# cellular.net
KiCad netlist of a schematic drawn in Altium Designer
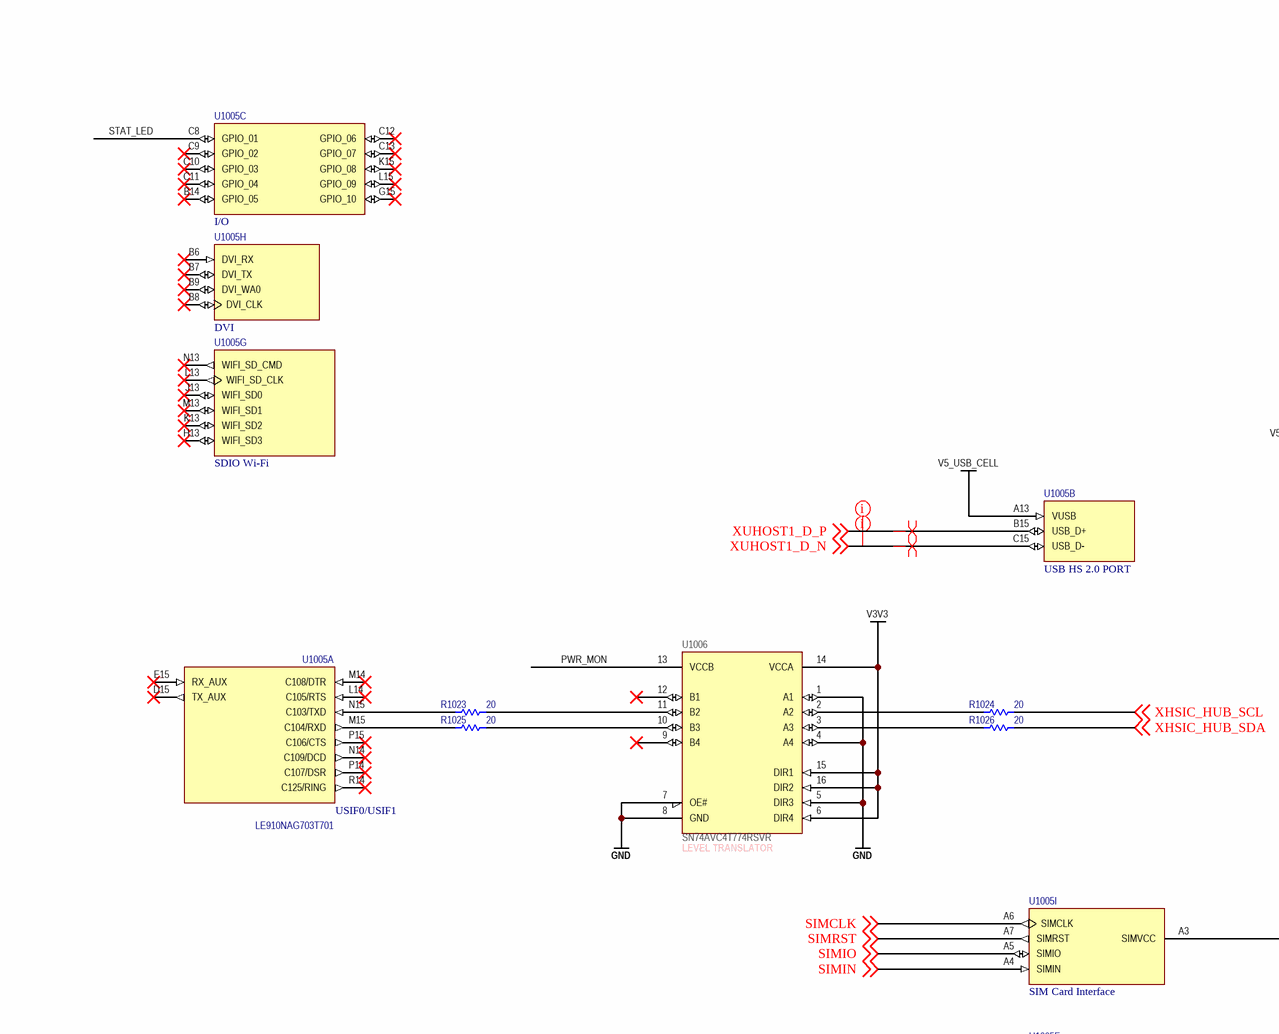
[diagram p0: cellular.SchDoc, top left]
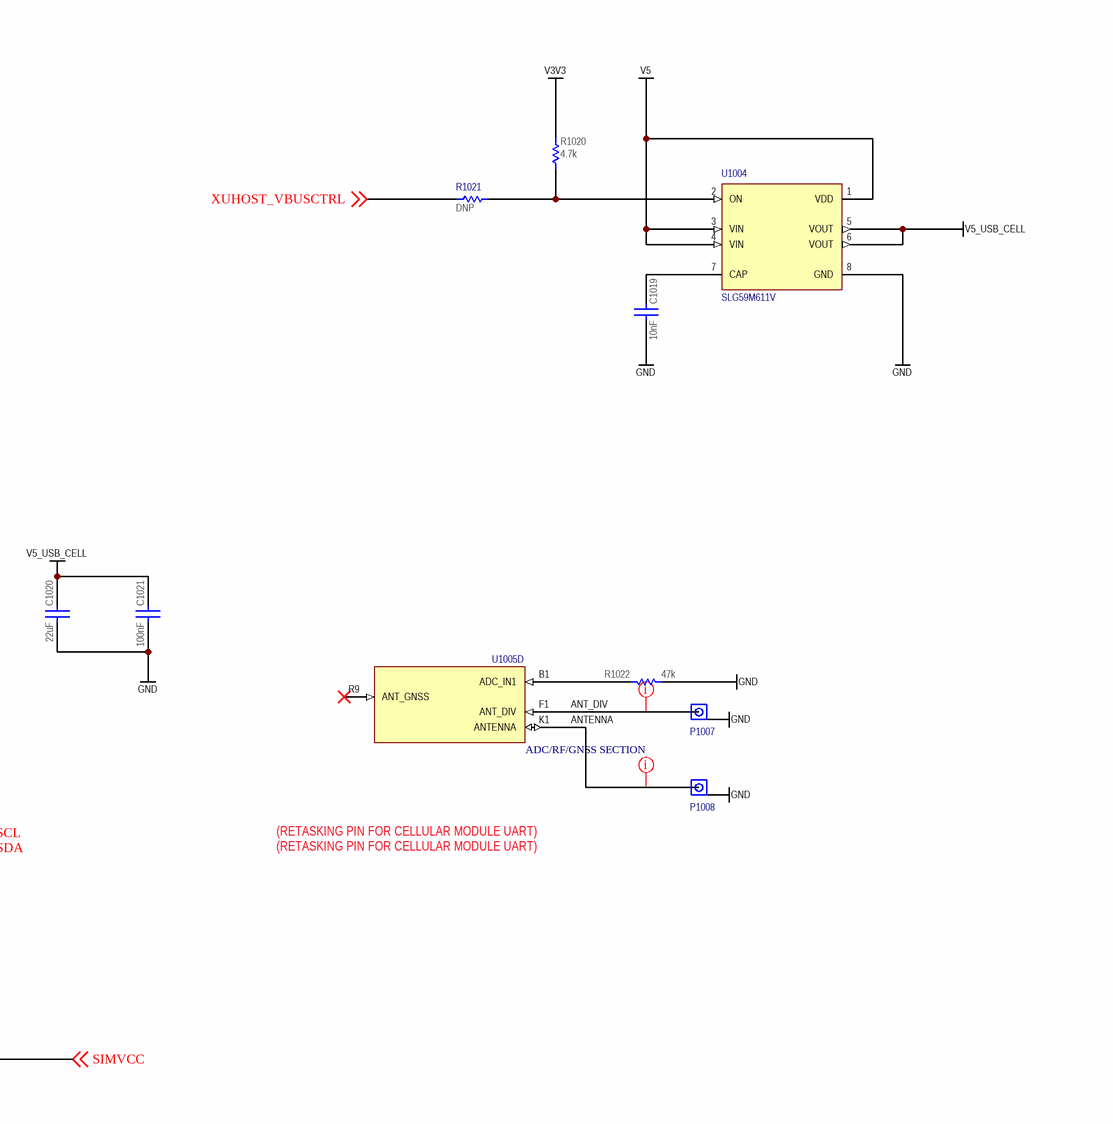
[diagram p1: cellular.SchDoc, top right]
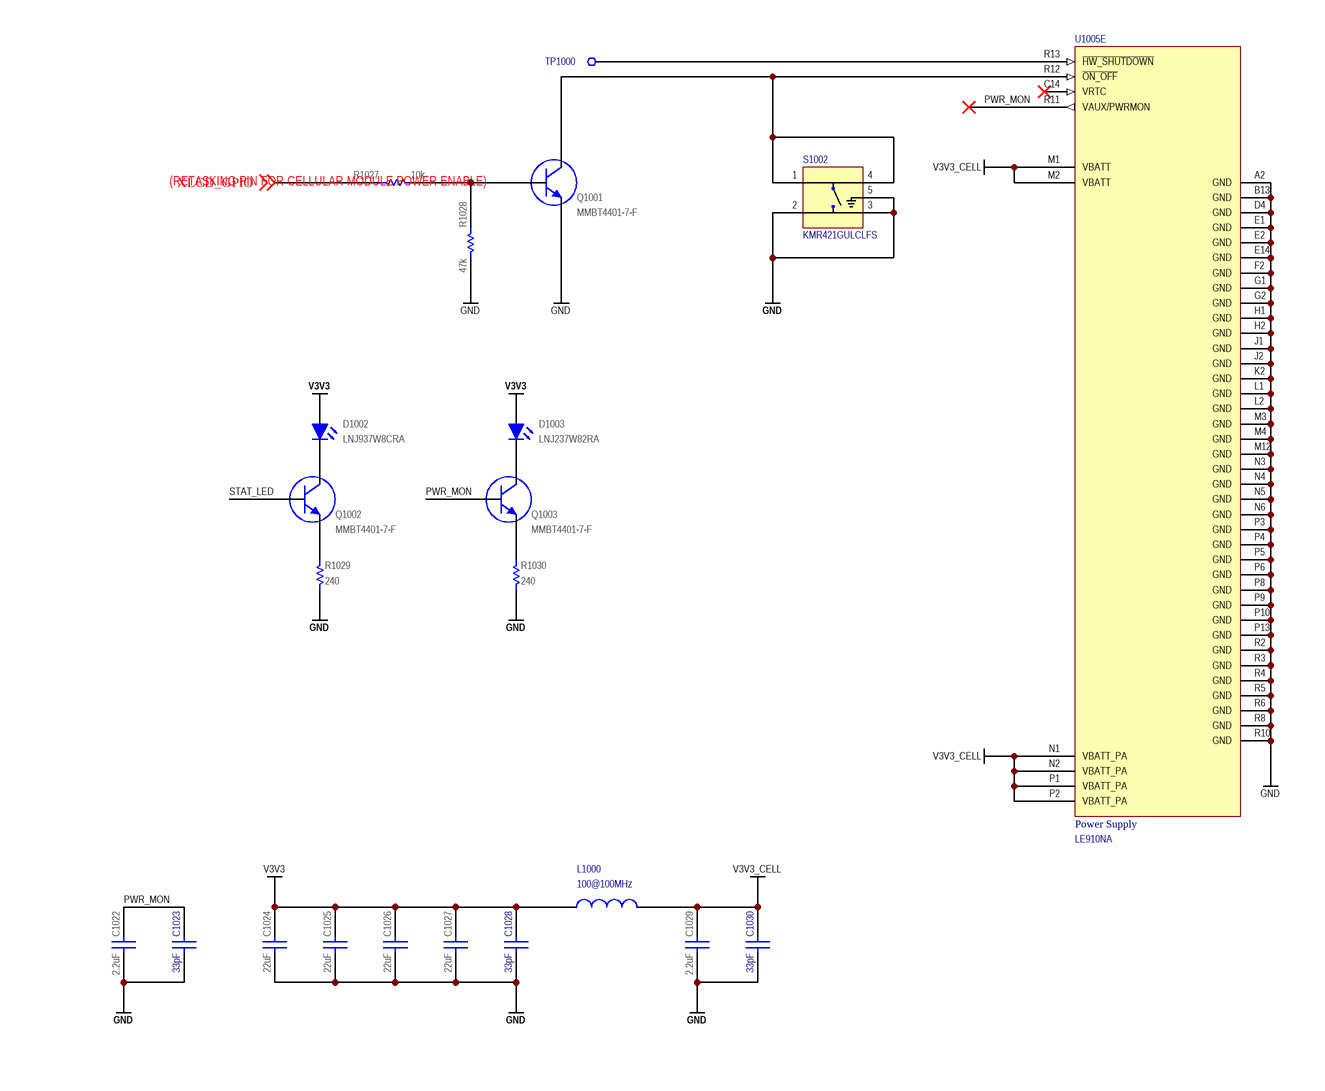
[diagram p2: cellular.SchDoc, bottom left]
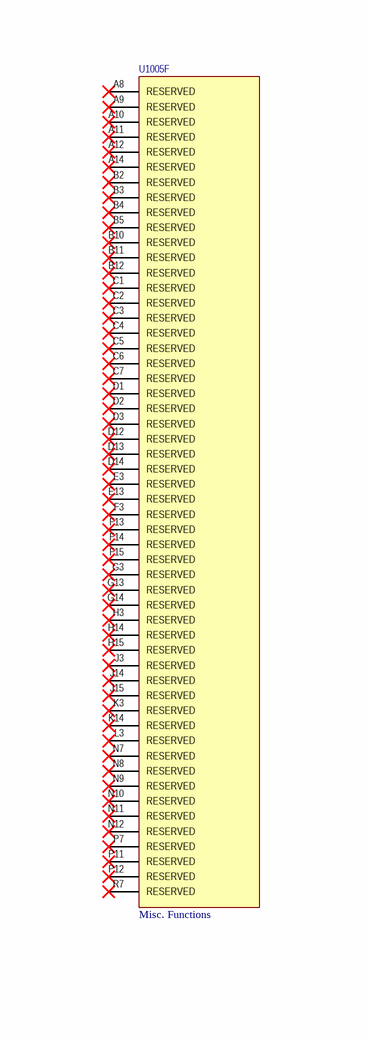
[diagram p3: cellular.SchDoc, bottom right]

(export (version "E")
  (design (tool "Eeschema 10.0.6"))
  (components
    (comp (ref "C1019")
      (value "10nF")
      (footprint "CAPC100X50X55L25N")
      (description "Ceramic Capacitor 10nF ±10% 50V X7R 0402")
      (fields (field (name "MANUFACTURER") "Murata") (field (name "TOLERANCE") "±10%"))
      (libsource (lib "generic") (part "CAP"))
    )
    (comp (ref "C1020")
      (value "22uF")
      (footprint "CAPC200X125X145L45N")
      (description "Ceramic Capacitor 22uF ±20% 10V X7S 0805")
      (fields (field (name "MANUFACTURER") "TDK") (field (name "TOLERANCE") "±20%"))
      (libsource (lib "generic") (part "CAP"))
    )
    (comp (ref "C1021")
      (value "100nF")
      (footprint "CAPC100X50X55L25N")
      (description "Ceramic Capacitor 100nF ±10% 50V X7R 0402")
      (fields (field (name "MANUFACTURER") "Murata") (field (name "TOLERANCE") "±10%"))
      (libsource (lib "generic") (part "CAP"))
    )
    (comp (ref "C1022")
      (value "2.2uF")
      (footprint "CAPC160X80X90L20N")
      (description "Ceramic Capacitor 2.2uF ±20% 10V X7R 0603")
      (fields (field (name "MANUFACTURER") "TDK") (field (name "TOLERANCE") "±20%"))
      (libsource (lib "generic") (part "CAP"))
    )
    (comp (ref "C1023")
      (value "33pF")
      (footprint "0402")
      (description "Ceramic Capacitor 33pF ±1% 50V NP0 0402")
      (fields (field (name "VOLTAGE") "50V") (field (name "MANUFACTURER") "Kemet"))
      (libsource (lib "Graviton") (part "CAP 0603"))
    )
    (comp (ref "C1024")
      (value "22uF")
      (footprint "CAPC200X125X145L45N")
      (description "Ceramic Capacitor 22uF ±20% 10V X7S 0805")
      (fields (field (name "MANUFACTURER") "TDK") (field (name "TOLERANCE") "±20%"))
      (libsource (lib "generic") (part "CAP"))
    )
    (comp (ref "C1025")
      (value "22uF")
      (footprint "CAPC200X125X145L45N")
      (description "Ceramic Capacitor 22uF ±20% 10V X7S 0805")
      (fields (field (name "MANUFACTURER") "TDK") (field (name "TOLERANCE") "±20%"))
      (libsource (lib "generic") (part "CAP"))
    )
    (comp (ref "C1026")
      (value "22uF")
      (footprint "CAPC200X125X145L45N")
      (description "Ceramic Capacitor 22uF ±20% 10V X7S 0805")
      (fields (field (name "MANUFACTURER") "TDK") (field (name "TOLERANCE") "±20%"))
      (libsource (lib "generic") (part "CAP"))
    )
    (comp (ref "C1027")
      (value "22uF")
      (footprint "CAPC200X125X145L45N")
      (description "Ceramic Capacitor 22uF ±20% 10V X7S 0805")
      (fields (field (name "MANUFACTURER") "TDK") (field (name "TOLERANCE") "±20%"))
      (libsource (lib "generic") (part "CAP"))
    )
    (comp (ref "C1028")
      (value "33pF")
      (footprint "0402")
      (description "Ceramic Capacitor 33pF ±1% 50V NP0 0402")
      (fields (field (name "VOLTAGE") "50V") (field (name "MANUFACTURER") "Kemet"))
      (libsource (lib "Graviton") (part "CAP 0603"))
    )
    (comp (ref "C1029")
      (value "2.2uF")
      (footprint "CAPC160X80X90L20N")
      (description "Ceramic Capacitor 2.2uF ±20% 10V X7R 0603")
      (fields (field (name "MANUFACTURER") "TDK") (field (name "TOLERANCE") "±20%"))
      (libsource (lib "generic") (part "CAP"))
    )
    (comp (ref "C1030")
      (value "33pF")
      (footprint "0402")
      (description "Ceramic Capacitor 33pF ±1% 50V NP0 0402")
      (fields (field (name "VOLTAGE") "50V") (field (name "MANUFACTURER") "Kemet"))
      (libsource (lib "Graviton") (part "CAP 0603"))
    )
    (comp (ref "D1002")
      (value "LNJ937W8CRA")
      (footprint "0603_LED")
      (description "LED, SMT 0603, Color Blue, 5mA, 2.9V")
      (fields (field (name "MANUFACTURER") "Panasonic"))
      (libsource (lib "generic") (part "LED0603GR"))
    )
    (comp (ref "D1003")
      (value "LNJ237W82RA")
      (footprint "0603_LED")
      (description "LED, SMT 0603, Color Red, 5mA, 1.85V")
      (fields (field (name "MANUFACTURER") "Panasonic"))
      (libsource (lib "generic") (part "LED0603RD"))
    )
    (comp (ref "L1000")
      (value "100@100MHz")
      (footprint "generic:0603")
      (description "Ferrite Bead 100-Ohm @ 100MHz 2A 0603")
      (fields (field (name "MANUFACTURER") "Murata") (field (name "TOLERANCE") "±25%"))
      (libsource (lib "altium-import") (part "root_0_IND 0402_"))
    )
    (comp (ref "P1007")
      (value "U.FL-R-SMT(10)")
      (footprint "U.FL-R-SMT(10)")
      (description "Ultra Miniature Coaxial Jack, 50 Ohms")
      (fields (field (name "MANUFACTURER") "Hirose"))
      (libsource (lib "hirose") (part "U.FL-R-SMT(10)"))
    )
    (comp (ref "P1008")
      (value "U.FL-R-SMT(10)")
      (footprint "U.FL-R-SMT(10)")
      (description "Ultra Miniature Coaxial Jack, 50 Ohms")
      (fields (field (name "MANUFACTURER") "Hirose"))
      (libsource (lib "hirose") (part "U.FL-R-SMT(10)"))
    )
    (comp (ref "Q1001")
      (value "MMBT4401-7-F")
      (footprint "generic:SOT23")
      (description "NPN Small Signal Transistor SMD SOT-23")
      (fields (field (name "MANUFACTURER P/N") "MMBT4401-7-F") (field (name "MANUFACTURER") "Diodes, Inc."))
      (libsource (lib "diodes_inc") (part "MMBT4401-7-F"))
    )
    (comp (ref "Q1002")
      (value "MMBT4401-7-F")
      (footprint "generic:SOT23")
      (description "NPN Small Signal Transistor SMD SOT-23")
      (fields (field (name "MANUFACTURER P/N") "MMBT4401-7-F") (field (name "MANUFACTURER") "Diodes, Inc."))
      (libsource (lib "diodes_inc") (part "MMBT4401-7-F"))
    )
    (comp (ref "Q1003")
      (value "MMBT4401-7-F")
      (footprint "generic:SOT23")
      (description "NPN Small Signal Transistor SMD SOT-23")
      (fields (field (name "MANUFACTURER P/N") "MMBT4401-7-F") (field (name "MANUFACTURER") "Diodes, Inc."))
      (libsource (lib "diodes_inc") (part "MMBT4401-7-F"))
    )
    (comp (ref "R1020")
      (value "4.7k")
      (footprint "RESC1005X40N")
      (description "Thick Film Resistor 4.7k ±1% 0.1W 75V 0402")
      (fields (field (name "TOLERANCE") "±1%") (field (name "MANUFACTURER") "Panasonic"))
      (libsource (lib "generic") (part "RES"))
    )
    (comp (ref "R1021")
      (value "ERJ-2RKF20R0X")
      (footprint "generic:0402")
      (description "Thick Film Resistor 20 ±1% 0402")
      (fields
        (field (name "MANUFACTURER") "Panasonic")
        (field (name "TOLERANCE") "±1%")
        (field (name "DO NOT PLACE") "DNP")
      )
      (libsource (lib "altium-import") (part "root_2_RES 0402_"))
    )
    (comp (ref "R1022")
      (value "47k")
      (footprint "RESC1005X40N")
      (description "Thick Film Resistor 47k ±1% 0.1W 75V 0402")
      (fields (field (name "TOLERANCE") "±1%") (field (name "MANUFACTURER") "Panasonic"))
      (libsource (lib "generic") (part "RES"))
    )
    (comp (ref "R1023")
      (value "20")
      (footprint "generic:0402")
      (description "Thick Film Resistor 20 ±1% 0402")
      (fields (field (name "MANUFACTURER") "Panasonic") (field (name "TOLERANCE") "±1%"))
      (libsource (lib "altium-import") (part "root_2_RES 0402_"))
    )
    (comp (ref "R1024")
      (value "20")
      (footprint "generic:0402")
      (description "Thick Film Resistor 20 ±1% 0402")
      (fields (field (name "MANUFACTURER") "Panasonic") (field (name "TOLERANCE") "±1%"))
      (libsource (lib "altium-import") (part "root_2_RES 0402_"))
    )
    (comp (ref "R1025")
      (value "20")
      (footprint "generic:0402")
      (description "Thick Film Resistor 20 ±1% 0402")
      (fields (field (name "MANUFACTURER") "Panasonic") (field (name "TOLERANCE") "±1%"))
      (libsource (lib "altium-import") (part "root_2_RES 0402_"))
    )
    (comp (ref "R1026")
      (value "20")
      (footprint "generic:0402")
      (description "Thick Film Resistor 20 ±1% 0402")
      (fields (field (name "MANUFACTURER") "Panasonic") (field (name "TOLERANCE") "±1%"))
      (libsource (lib "altium-import") (part "root_2_RES 0402_"))
    )
    (comp (ref "R1027")
      (value "10k")
      (footprint "RESC1005X40N")
      (description "Thick Film Resistor 10k ±1% 0.1W 0402")
      (fields (field (name "TOLERANCE") "±1%") (field (name "MANUFACTURER") "Panasonic"))
      (libsource (lib "generic") (part "RES"))
    )
    (comp (ref "R1028")
      (value "47k")
      (footprint "RESC1005X40N")
      (description "Thick Film Resistor 47k ±1% 0.1W 75V 0402")
      (fields (field (name "TOLERANCE") "±1%") (field (name "MANUFACTURER") "Panasonic"))
      (libsource (lib "generic") (part "RES"))
    )
    (comp (ref "R1029")
      (value "240")
      (footprint "RESC1005X40N")
      (description "Thick Film Resistor 240 ±1% 0.1W 75V 0402")
      (fields (field (name "TOLERANCE") "±1%") (field (name "MANUFACTURER") "Panasonic"))
      (libsource (lib "generic") (part "RES"))
    )
    (comp (ref "R1030")
      (value "240")
      (footprint "RESC1005X40N")
      (description "Thick Film Resistor 240 ±1% 0.1W 75V 0402")
      (fields (field (name "TOLERANCE") "±1%") (field (name "MANUFACTURER") "Panasonic"))
      (libsource (lib "generic") (part "RES"))
    )
    (comp (ref "S1002")
      (value "KMR421GULCLFS")
      (footprint "SW_KMR421GULCLFS")
      (description "Switch Tactile N.O. SPST Round Button Gull Wing 0.05A 32VDC 1VA 200000Cycles 2N SMD Automotive T/R")
      (fields (field (name "MANUFACTURER") "C&K Components"))
      (libsource (lib "c&k") (part "KMR421GULCLFS"))
    )
    (comp (ref "TP1000")
      (value "TEST_POINT_SMD_10")
      (footprint "generic:TEST_POINT_SMD_10")
      (description "Test Point SMD")
      (libsource (lib "generic") (part "TEST_POINT_SMD_10"))
    )
    (comp (ref "U1004")
      (value "SLG59M611V")
      (footprint "DFN200X150X80-8N")
      (description "High-Side Load Switch")
      (fields (field (name "MANUFACTURER") "Silego"))
      (libsource (lib "silego") (part "SLG59M611V"))
    )
    (comp (ref "U1005")
      (value "LE910NAG703T701")
      (footprint "LGA144S180P15X15_2820X2820X225_LE910NAG703T701(Primary)")
      (description "LE910 North America (AT&T, T-Mobile)")
      (fields (field (name "MANUFACTURER") "Telit") (field (name "MANUFACTURER P/N") "LE910NA"))
      (libsource (lib "") (part "LE910NAG703T701_1"))
    )
    (comp (ref "U1006")
      (value "SN74AVC4T774RSVR")
      (footprint "RSV")
      (description "4-Bit Dual-Supply Bus Transceiver")
      (fields (field (name "MANUFACTURER") "Texas Instruments"))
      (libsource (lib "ti") (part "SN74AVC4T774RSVR"))
    )
  )
  (nets
    (net (code "1") (name "/ANTENNA") (class "Default")
      (node (ref "P1008") (pin "1") (pinfunction "RF_1") (pintype "passive"))
      (node (ref "U1005") (pin "K1") (pinfunction "ANTENNA_K1") (pintype "bidirectional"))
    )
    (net (code "2") (name "/ANT_DIV") (class "Default")
      (node (ref "P1007") (pin "1") (pinfunction "RF_1") (pintype "passive"))
      (node (ref "U1005") (pin "F1") (pinfunction "ANT_DIV_F1") (pintype "input"))
    )
    (net (code "3") (name "/PWR_MON") (class "Default")
      (node (ref "C1022") (pin "2") (pinfunction "2_2") (pintype "passive"))
      (node (ref "C1023") (pin "1") (pinfunction "1_1") (pintype "passive"))
      (node (ref "Q1003") (pin "1") (pinfunction "B_1") (pintype "passive"))
      (node (ref "U1005") (pin "R11") (pinfunction "VAUX/PWRMON_R11") (pintype "output"))
      (node (ref "U1006") (pin "13") (pinfunction "VCCB_13") (pintype "power_in"))
    )
    (net (code "4") (name "/STAT_LED") (class "Default")
      (node (ref "Q1002") (pin "1") (pinfunction "B_1") (pintype "passive"))
      (node (ref "U1005") (pin "C8") (pinfunction "GPIO_01_C8") (pintype "bidirectional"))
    )
    (net (code "5") (name "GND") (class "Default")
      (node (ref "C1019") (pin "1") (pinfunction "1_1") (pintype "passive"))
      (node (ref "C1020") (pin "1") (pinfunction "1_1") (pintype "passive"))
      (node (ref "C1021") (pin "1") (pinfunction "1_1") (pintype "passive"))
      (node (ref "C1022") (pin "1") (pinfunction "1_1") (pintype "passive"))
      (node (ref "C1023") (pin "2") (pinfunction "2_2") (pintype "passive"))
      (node (ref "C1024") (pin "1") (pinfunction "1_1") (pintype "passive"))
      (node (ref "C1025") (pin "1") (pinfunction "1_1") (pintype "passive"))
      (node (ref "C1026") (pin "1") (pinfunction "1_1") (pintype "passive"))
      (node (ref "C1027") (pin "1") (pinfunction "1_1") (pintype "passive"))
      (node (ref "C1028") (pin "2") (pinfunction "2_2") (pintype "passive"))
      (node (ref "C1029") (pin "1") (pinfunction "1_1") (pintype "passive"))
      (node (ref "C1030") (pin "2") (pinfunction "2_2") (pintype "passive"))
      (node (ref "P1007") (pin "2") (pinfunction "GND_2") (pintype "passive"))
      (node (ref "P1008") (pin "2") (pinfunction "GND_2") (pintype "passive"))
      (node (ref "Q1001") (pin "2") (pinfunction "E_2") (pintype "passive"))
      (node (ref "R1022") (pin "1") (pinfunction "1_1") (pintype "passive"))
      (node (ref "R1028") (pin "1") (pinfunction "1_1") (pintype "passive"))
      (node (ref "R1029") (pin "2") (pinfunction "2_2") (pintype "passive"))
      (node (ref "R1030") (pin "2") (pinfunction "2_2") (pintype "passive"))
      (node (ref "S1002") (pin "2") (pinfunction "2_2") (pintype "passive"))
      (node (ref "S1002") (pin "3") (pinfunction "3_3") (pintype "passive"))
      (node (ref "S1002") (pin "5") (pinfunction "G_5") (pintype "power_in"))
      (node (ref "U1004") (pin "8") (pinfunction "GND_8") (pintype "power_in"))
      (node (ref "U1005") (pin "A2") (pinfunction "GND_A2") (pintype "power_in"))
      (node (ref "U1005") (pin "B13") (pinfunction "GND_B13") (pintype "power_in"))
      (node (ref "U1005") (pin "D4") (pinfunction "GND_D4") (pintype "power_in"))
      (node (ref "U1005") (pin "E1") (pinfunction "GND_E1") (pintype "power_in"))
      (node (ref "U1005") (pin "E14") (pinfunction "GND_E14") (pintype "power_in"))
      (node (ref "U1005") (pin "E2") (pinfunction "GND_E2") (pintype "power_in"))
      (node (ref "U1005") (pin "F2") (pinfunction "GND_F2") (pintype "power_in"))
      (node (ref "U1005") (pin "G1") (pinfunction "GND_G1") (pintype "power_in"))
      (node (ref "U1005") (pin "G2") (pinfunction "GND_G2") (pintype "power_in"))
      (node (ref "U1005") (pin "H1") (pinfunction "GND_H1") (pintype "power_in"))
      (node (ref "U1005") (pin "H2") (pinfunction "GND_H2") (pintype "power_in"))
      (node (ref "U1005") (pin "J1") (pinfunction "GND_J1") (pintype "power_in"))
      (node (ref "U1005") (pin "J2") (pinfunction "GND_J2") (pintype "power_in"))
      (node (ref "U1005") (pin "K2") (pinfunction "GND_K2") (pintype "power_in"))
      (node (ref "U1005") (pin "L1") (pinfunction "GND_L1") (pintype "power_in"))
      (node (ref "U1005") (pin "L2") (pinfunction "GND_L2") (pintype "power_in"))
      (node (ref "U1005") (pin "M12") (pinfunction "GND_M12") (pintype "power_in"))
      (node (ref "U1005") (pin "M3") (pinfunction "GND_M3") (pintype "power_in"))
      (node (ref "U1005") (pin "M4") (pinfunction "GND_M4") (pintype "power_in"))
      (node (ref "U1005") (pin "N3") (pinfunction "GND_N3") (pintype "power_in"))
      (node (ref "U1005") (pin "N4") (pinfunction "GND_N4") (pintype "power_in"))
      (node (ref "U1005") (pin "N5") (pinfunction "GND_N5") (pintype "power_in"))
      (node (ref "U1005") (pin "N6") (pinfunction "GND_N6") (pintype "power_in"))
      (node (ref "U1005") (pin "P10") (pinfunction "GND_P10") (pintype "power_in"))
      (node (ref "U1005") (pin "P13") (pinfunction "GND_P13") (pintype "power_in"))
      (node (ref "U1005") (pin "P3") (pinfunction "GND_P3") (pintype "power_in"))
      (node (ref "U1005") (pin "P4") (pinfunction "GND_P4") (pintype "power_in"))
      (node (ref "U1005") (pin "P5") (pinfunction "GND_P5") (pintype "power_in"))
      (node (ref "U1005") (pin "P6") (pinfunction "GND_P6") (pintype "power_in"))
      (node (ref "U1005") (pin "P8") (pinfunction "GND_P8") (pintype "power_in"))
      (node (ref "U1005") (pin "P9") (pinfunction "GND_P9") (pintype "power_in"))
      (node (ref "U1005") (pin "R10") (pinfunction "GND_R10") (pintype "power_in"))
      (node (ref "U1005") (pin "R2") (pinfunction "GND_R2") (pintype "power_in"))
      (node (ref "U1005") (pin "R3") (pinfunction "GND_R3") (pintype "power_in"))
      (node (ref "U1005") (pin "R4") (pinfunction "GND_R4") (pintype "power_in"))
      (node (ref "U1005") (pin "R5") (pinfunction "GND_R5") (pintype "power_in"))
      (node (ref "U1005") (pin "R6") (pinfunction "GND_R6") (pintype "power_in"))
      (node (ref "U1005") (pin "R8") (pinfunction "GND_R8") (pintype "power_in"))
      (node (ref "U1006") (pin "1") (pinfunction "A1_1") (pintype "bidirectional"))
      (node (ref "U1006") (pin "4") (pinfunction "A4_4") (pintype "bidirectional"))
      (node (ref "U1006") (pin "5") (pinfunction "DIR3_5") (pintype "input"))
      (node (ref "U1006") (pin "7") (pinfunction "OE#_7") (pintype "passive"))
      (node (ref "U1006") (pin "8") (pinfunction "GND_8") (pintype "power_in"))
    )
    (net (code "6") (name "Net-(D1002-K)") (class "Default")
      (node (ref "D1002") (pin "2") (pinfunction "K_2") (pintype "passive"))
      (node (ref "Q1002") (pin "3") (pinfunction "C_3") (pintype "passive"))
    )
    (net (code "7") (name "Net-(D1003-K)") (class "Default")
      (node (ref "D1003") (pin "2") (pinfunction "K_2") (pintype "passive"))
      (node (ref "Q1003") (pin "3") (pinfunction "C_3") (pintype "passive"))
    )
    (net (code "8") (name "Net-(Q1001-B)") (class "Default")
      (node (ref "Q1001") (pin "1") (pinfunction "B_1") (pintype "passive"))
      (node (ref "R1027") (pin "1") (pinfunction "1_1") (pintype "passive"))
      (node (ref "R1028") (pin "2") (pinfunction "2_2") (pintype "passive"))
    )
    (net (code "9") (name "Net-(Q1001-C)") (class "Default")
      (node (ref "Q1001") (pin "3") (pinfunction "C_3") (pintype "passive"))
      (node (ref "S1002") (pin "1") (pinfunction "1_1") (pintype "passive"))
      (node (ref "S1002") (pin "4") (pinfunction "4_4") (pintype "passive"))
      (node (ref "U1005") (pin "R12") (pinfunction "~{ON_OFF}_R12") (pintype "input"))
    )
    (net (code "10") (name "Net-(Q1002-E)") (class "Default")
      (node (ref "Q1002") (pin "2") (pinfunction "E_2") (pintype "passive"))
      (node (ref "R1029") (pin "1") (pinfunction "1_1") (pintype "passive"))
    )
    (net (code "11") (name "Net-(Q1003-E)") (class "Default")
      (node (ref "Q1003") (pin "2") (pinfunction "E_2") (pintype "passive"))
      (node (ref "R1030") (pin "1") (pinfunction "1_1") (pintype "passive"))
    )
    (net (code "12") (name "Net-(U1004-CAP)") (class "Default")
      (node (ref "C1019") (pin "2") (pinfunction "2_2") (pintype "passive"))
      (node (ref "U1004") (pin "7") (pinfunction "CAP_7") (pintype "passive"))
    )
    (net (code "13") (name "Net-(U1004-ON)") (class "Default")
      (node (ref "R1020") (pin "1") (pinfunction "1_1") (pintype "passive"))
      (node (ref "R1021") (pin "1") (pinfunction "1_1") (pintype "passive"))
      (node (ref "U1004") (pin "2") (pinfunction "ON_2") (pintype "input"))
    )
    (net (code "14") (name "Net-(U1005A-C103{slash}TXD)") (class "Default")
      (node (ref "R1023") (pin "2") (pinfunction "2_2") (pintype "passive"))
      (node (ref "U1005") (pin "N15") (pinfunction "C103/TXD_N15") (pintype "input"))
    )
    (net (code "15") (name "Net-(U1005A-C104{slash}RXD)") (class "Default")
      (node (ref "R1025") (pin "2") (pinfunction "2_2") (pintype "passive"))
      (node (ref "U1005") (pin "M15") (pinfunction "C104/RXD_M15") (pintype "output"))
    )
    (net (code "16") (name "Net-(U1005D-ADC_IN1)") (class "Default")
      (node (ref "R1022") (pin "2") (pinfunction "2_2") (pintype "passive"))
      (node (ref "U1005") (pin "B1") (pinfunction "ADC_IN1_B1") (pintype "input"))
    )
    (net (code "17") (name "Net-(U1005E-~{HW_SHUTDOWN})") (class "Default")
      (node (ref "TP1000") (pin "1") (pinfunction "1_1") (pintype "passive"))
      (node (ref "U1005") (pin "R13") (pinfunction "~{HW_SHUTDOWN}_R13") (pintype "input"))
    )
    (net (code "18") (name "Net-(U1006-A2)") (class "Default")
      (node (ref "R1024") (pin "2") (pinfunction "2_2") (pintype "passive"))
      (node (ref "U1006") (pin "2") (pinfunction "A2_2") (pintype "bidirectional"))
    )
    (net (code "19") (name "Net-(U1006-A3)") (class "Default")
      (node (ref "R1026") (pin "2") (pinfunction "2_2") (pintype "passive"))
      (node (ref "U1006") (pin "3") (pinfunction "A3_3") (pintype "bidirectional"))
    )
    (net (code "20") (name "Net-(U1006-B2)") (class "Default")
      (node (ref "R1023") (pin "1") (pinfunction "1_1") (pintype "passive"))
      (node (ref "U1006") (pin "11") (pinfunction "B2_11") (pintype "bidirectional"))
    )
    (net (code "21") (name "Net-(U1006-B3)") (class "Default")
      (node (ref "R1025") (pin "1") (pinfunction "1_1") (pintype "passive"))
      (node (ref "U1006") (pin "10") (pinfunction "B3_10") (pintype "bidirectional"))
    )
    (net (code "22") (name "SIMCLK") (class "Default")
      (node (ref "U1005") (pin "A6") (pinfunction "SIMCLK_A6") (pintype "output"))
    )
    (net (code "23") (name "SIMIN") (class "Default")
      (node (ref "U1005") (pin "A4") (pinfunction "SIMIN_A4") (pintype "input"))
    )
    (net (code "24") (name "SIMIO") (class "Default")
      (node (ref "U1005") (pin "A5") (pinfunction "SIMIO_A5") (pintype "bidirectional"))
    )
    (net (code "25") (name "SIMRST") (class "Default")
      (node (ref "U1005") (pin "A7") (pinfunction "SIMRST_A7") (pintype "output"))
    )
    (net (code "26") (name "SIMVCC") (class "Default")
      (node (ref "U1005") (pin "A3") (pinfunction "SIMVCC_A3") (pintype "power_in"))
    )
    (net (code "27") (name "V3V3") (class "Default")
      (node (ref "C1024") (pin "2") (pinfunction "2_2") (pintype "passive"))
      (node (ref "C1025") (pin "2") (pinfunction "2_2") (pintype "passive"))
      (node (ref "C1026") (pin "2") (pinfunction "2_2") (pintype "passive"))
      (node (ref "C1027") (pin "2") (pinfunction "2_2") (pintype "passive"))
      (node (ref "C1028") (pin "1") (pinfunction "1_1") (pintype "passive"))
      (node (ref "D1002") (pin "1") (pinfunction "A_1") (pintype "passive"))
      (node (ref "D1003") (pin "1") (pinfunction "A_1") (pintype "passive"))
      (node (ref "L1000") (pin "1") (pinfunction "1_1") (pintype "passive"))
      (node (ref "R1020") (pin "2") (pinfunction "2_2") (pintype "passive"))
      (node (ref "U1006") (pin "14") (pinfunction "VCCA_14") (pintype "power_in"))
      (node (ref "U1006") (pin "15") (pinfunction "DIR1_15") (pintype "input"))
      (node (ref "U1006") (pin "16") (pinfunction "DIR2_16") (pintype "input"))
      (node (ref "U1006") (pin "6") (pinfunction "DIR4_6") (pintype "input"))
    )
    (net (code "28") (name "V3V3_CELL") (class "Default")
      (node (ref "C1029") (pin "2") (pinfunction "2_2") (pintype "passive"))
      (node (ref "C1030") (pin "1") (pinfunction "1_1") (pintype "passive"))
      (node (ref "L1000") (pin "2") (pinfunction "2_2") (pintype "passive"))
      (node (ref "U1005") (pin "M1") (pinfunction "VBATT_M1") (pintype "power_in"))
      (node (ref "U1005") (pin "M2") (pinfunction "VBATT_M2") (pintype "power_in"))
      (node (ref "U1005") (pin "N1") (pinfunction "VBATT_PA_N1") (pintype "power_in"))
      (node (ref "U1005") (pin "N2") (pinfunction "VBATT_PA_N2") (pintype "power_in"))
      (node (ref "U1005") (pin "P1") (pinfunction "VBATT_PA_P1") (pintype "power_in"))
      (node (ref "U1005") (pin "P2") (pinfunction "VBATT_PA_P2") (pintype "power_in"))
    )
    (net (code "29") (name "V5") (class "Default")
      (node (ref "U1004") (pin "1") (pinfunction "VDD_1") (pintype "power_in"))
      (node (ref "U1004") (pin "3") (pinfunction "VIN_3") (pintype "input"))
      (node (ref "U1004") (pin "4") (pinfunction "VIN_4") (pintype "input"))
    )
    (net (code "30") (name "V5_USB_CELL") (class "Default")
      (node (ref "C1020") (pin "2") (pinfunction "2_2") (pintype "passive"))
      (node (ref "C1021") (pin "2") (pinfunction "2_2") (pintype "passive"))
      (node (ref "U1004") (pin "5") (pinfunction "VOUT_5") (pintype "output"))
      (node (ref "U1004") (pin "6") (pinfunction "VOUT_6") (pintype "output"))
      (node (ref "U1005") (pin "A13") (pinfunction "VUSB_A13") (pintype "input"))
    )
    (net (code "31") (name "XHSIC_HUB_SCL") (class "Default")
      (node (ref "R1024") (pin "1") (pinfunction "1_1") (pintype "passive"))
    )
    (net (code "32") (name "XHSIC_HUB_SDA") (class "Default")
      (node (ref "R1026") (pin "1") (pinfunction "1_1") (pintype "passive"))
    )
    (net (code "33") (name "XLCD_GPIO") (class "Default")
      (node (ref "R1027") (pin "2") (pinfunction "2_2") (pintype "passive"))
    )
    (net (code "34") (name "XUHOST1_D_N") (class "Default")
      (node (ref "U1005") (pin "C15") (pinfunction "USB_D-_C15") (pintype "bidirectional"))
    )
    (net (code "35") (name "XUHOST1_D_P") (class "Default")
      (node (ref "U1005") (pin "B15") (pinfunction "USB_D+_B15") (pintype "bidirectional"))
    )
    (net (code "36") (name "XUHOST_VBUSCTRL") (class "Default")
      (node (ref "R1021") (pin "2") (pinfunction "2_2") (pintype "passive"))
    )
    (net (code "37") (name "unconnected-(U1005A-C105{slash}RTS-PadL14)") (class "Default")
      (node (ref "U1005") (pin "L14") (pinfunction "C105/RTS_L14") (pintype "input+no_connect"))
    )
    (net (code "38") (name "unconnected-(U1005A-C106{slash}CTS-PadP15)") (class "Default")
      (node (ref "U1005") (pin "P15") (pinfunction "C106/CTS_P15") (pintype "output+no_connect"))
    )
    (net (code "39") (name "unconnected-(U1005A-C107{slash}DSR-PadP14)") (class "Default")
      (node (ref "U1005") (pin "P14") (pinfunction "C107/DSR_P14") (pintype "output+no_connect"))
    )
    (net (code "40") (name "unconnected-(U1005A-C108{slash}DTR-PadM14)") (class "Default")
      (node (ref "U1005") (pin "M14") (pinfunction "C108/DTR_M14") (pintype "input+no_connect"))
    )
    (net (code "41") (name "unconnected-(U1005A-C109{slash}DCD-PadN14)") (class "Default")
      (node (ref "U1005") (pin "N14") (pinfunction "C109/DCD_N14") (pintype "output+no_connect"))
    )
    (net (code "42") (name "unconnected-(U1005A-C125{slash}RING-PadR14)") (class "Default")
      (node (ref "U1005") (pin "R14") (pinfunction "C125/RING_R14") (pintype "output+no_connect"))
    )
    (net (code "43") (name "unconnected-(U1005A-RX_AUX-PadE15)") (class "Default")
      (node (ref "U1005") (pin "E15") (pinfunction "RX_AUX_E15") (pintype "input+no_connect"))
    )
    (net (code "44") (name "unconnected-(U1005A-TX_AUX-PadD15)") (class "Default")
      (node (ref "U1005") (pin "D15") (pinfunction "TX_AUX_D15") (pintype "output+no_connect"))
    )
    (net (code "45") (name "unconnected-(U1005C-GPIO_02-PadC9)") (class "Default")
      (node (ref "U1005") (pin "C9") (pinfunction "GPIO_02_C9") (pintype "bidirectional+no_connect"))
    )
    (net (code "46") (name "unconnected-(U1005C-GPIO_03-PadC10)") (class "Default")
      (node (ref "U1005") (pin "C10") (pinfunction "GPIO_03_C10") (pintype "bidirectional+no_connect"))
    )
    (net (code "47") (name "unconnected-(U1005C-GPIO_04-PadC11)") (class "Default")
      (node (ref "U1005") (pin "C11") (pinfunction "GPIO_04_C11") (pintype "bidirectional+no_connect"))
    )
    (net (code "48") (name "unconnected-(U1005C-GPIO_05-PadB14)") (class "Default")
      (node (ref "U1005") (pin "B14") (pinfunction "GPIO_05_B14") (pintype "bidirectional+no_connect"))
    )
    (net (code "49") (name "unconnected-(U1005C-GPIO_06-PadC12)") (class "Default")
      (node (ref "U1005") (pin "C12") (pinfunction "GPIO_06_C12") (pintype "bidirectional+no_connect"))
    )
    (net (code "50") (name "unconnected-(U1005C-GPIO_07-PadC13)") (class "Default")
      (node (ref "U1005") (pin "C13") (pinfunction "GPIO_07_C13") (pintype "bidirectional+no_connect"))
    )
    (net (code "51") (name "unconnected-(U1005C-GPIO_08-PadK15)") (class "Default")
      (node (ref "U1005") (pin "K15") (pinfunction "GPIO_08_K15") (pintype "bidirectional+no_connect"))
    )
    (net (code "52") (name "unconnected-(U1005C-GPIO_09-PadL15)") (class "Default")
      (node (ref "U1005") (pin "L15") (pinfunction "GPIO_09_L15") (pintype "bidirectional+no_connect"))
    )
    (net (code "53") (name "unconnected-(U1005C-GPIO_10-PadG15)") (class "Default")
      (node (ref "U1005") (pin "G15") (pinfunction "GPIO_10_G15") (pintype "bidirectional+no_connect"))
    )
    (net (code "54") (name "unconnected-(U1005D-ANT_GNSS-PadR9)") (class "Default")
      (node (ref "U1005") (pin "R9") (pinfunction "ANT_GNSS_R9") (pintype "input+no_connect"))
    )
    (net (code "55") (name "unconnected-(U1005E-VRTC-PadC14)") (class "Default")
      (node (ref "U1005") (pin "C14") (pinfunction "VRTC_C14") (pintype "input+no_connect"))
    )
    (net (code "56") (name "unconnected-(U1005F-RESERVED-PadA8)") (class "Default")
      (node (ref "U1005") (pin "A8") (pinfunction "RESERVED_A8") (pintype "passive+no_connect"))
    )
    (net (code "57") (name "unconnected-(U1005F-RESERVED-PadA9)") (class "Default")
      (node (ref "U1005") (pin "A9") (pinfunction "RESERVED_A9") (pintype "passive+no_connect"))
    )
    (net (code "58") (name "unconnected-(U1005F-RESERVED-PadA10)") (class "Default")
      (node (ref "U1005") (pin "A10") (pinfunction "RESERVED_A10") (pintype "passive+no_connect"))
    )
    (net (code "59") (name "unconnected-(U1005F-RESERVED-PadA11)") (class "Default")
      (node (ref "U1005") (pin "A11") (pinfunction "RESERVED_A11") (pintype "passive+no_connect"))
    )
    (net (code "60") (name "unconnected-(U1005F-RESERVED-PadA12)") (class "Default")
      (node (ref "U1005") (pin "A12") (pinfunction "RESERVED_A12") (pintype "passive+no_connect"))
    )
    (net (code "61") (name "unconnected-(U1005F-RESERVED-PadA14)") (class "Default")
      (node (ref "U1005") (pin "A14") (pinfunction "RESERVED_A14") (pintype "passive+no_connect"))
    )
    (net (code "62") (name "unconnected-(U1005F-RESERVED-PadB2)") (class "Default")
      (node (ref "U1005") (pin "B2") (pinfunction "RESERVED_B2") (pintype "passive+no_connect"))
    )
    (net (code "63") (name "unconnected-(U1005F-RESERVED-PadB3)") (class "Default")
      (node (ref "U1005") (pin "B3") (pinfunction "RESERVED_B3") (pintype "passive+no_connect"))
    )
    (net (code "64") (name "unconnected-(U1005F-RESERVED-PadB4)") (class "Default")
      (node (ref "U1005") (pin "B4") (pinfunction "RESERVED_B4") (pintype "passive+no_connect"))
    )
    (net (code "65") (name "unconnected-(U1005F-RESERVED-PadB5)") (class "Default")
      (node (ref "U1005") (pin "B5") (pinfunction "RESERVED_B5") (pintype "passive+no_connect"))
    )
    (net (code "66") (name "unconnected-(U1005F-RESERVED-PadB10)") (class "Default")
      (node (ref "U1005") (pin "B10") (pinfunction "RESERVED_B10") (pintype "passive+no_connect"))
    )
    (net (code "67") (name "unconnected-(U1005F-RESERVED-PadB11)") (class "Default")
      (node (ref "U1005") (pin "B11") (pinfunction "RESERVED_B11") (pintype "passive+no_connect"))
    )
    (net (code "68") (name "unconnected-(U1005F-RESERVED-PadB12)") (class "Default")
      (node (ref "U1005") (pin "B12") (pinfunction "RESERVED_B12") (pintype "passive+no_connect"))
    )
    (net (code "69") (name "unconnected-(U1005F-RESERVED-PadC1)") (class "Default")
      (node (ref "U1005") (pin "C1") (pinfunction "RESERVED_C1") (pintype "passive+no_connect"))
    )
    (net (code "70") (name "unconnected-(U1005F-RESERVED-PadC2)") (class "Default")
      (node (ref "U1005") (pin "C2") (pinfunction "RESERVED_C2") (pintype "passive+no_connect"))
    )
    (net (code "71") (name "unconnected-(U1005F-RESERVED-PadC3)") (class "Default")
      (node (ref "U1005") (pin "C3") (pinfunction "RESERVED_C3") (pintype "passive+no_connect"))
    )
    (net (code "72") (name "unconnected-(U1005F-RESERVED-PadC4)") (class "Default")
      (node (ref "U1005") (pin "C4") (pinfunction "RESERVED_C4") (pintype "passive+no_connect"))
    )
    (net (code "73") (name "unconnected-(U1005F-RESERVED-PadC5)") (class "Default")
      (node (ref "U1005") (pin "C5") (pinfunction "RESERVED_C5") (pintype "passive+no_connect"))
    )
    (net (code "74") (name "unconnected-(U1005F-RESERVED-PadC6)") (class "Default")
      (node (ref "U1005") (pin "C6") (pinfunction "RESERVED_C6") (pintype "passive+no_connect"))
    )
    (net (code "75") (name "unconnected-(U1005F-RESERVED-PadC7)") (class "Default")
      (node (ref "U1005") (pin "C7") (pinfunction "RESERVED_C7") (pintype "passive+no_connect"))
    )
    (net (code "76") (name "unconnected-(U1005F-RESERVED-PadD1)") (class "Default")
      (node (ref "U1005") (pin "D1") (pinfunction "RESERVED_D1") (pintype "passive+no_connect"))
    )
    (net (code "77") (name "unconnected-(U1005F-RESERVED-PadD2)") (class "Default")
      (node (ref "U1005") (pin "D2") (pinfunction "RESERVED_D2") (pintype "passive+no_connect"))
    )
    (net (code "78") (name "unconnected-(U1005F-RESERVED-PadD3)") (class "Default")
      (node (ref "U1005") (pin "D3") (pinfunction "RESERVED_D3") (pintype "passive+no_connect"))
    )
    (net (code "79") (name "unconnected-(U1005F-RESERVED-PadD12)") (class "Default")
      (node (ref "U1005") (pin "D12") (pinfunction "RESERVED_D12") (pintype "passive+no_connect"))
    )
    (net (code "80") (name "unconnected-(U1005F-RESERVED-PadD13)") (class "Default")
      (node (ref "U1005") (pin "D13") (pinfunction "RESERVED_D13") (pintype "passive+no_connect"))
    )
    (net (code "81") (name "unconnected-(U1005F-RESERVED-PadD14)") (class "Default")
      (node (ref "U1005") (pin "D14") (pinfunction "RESERVED_D14") (pintype "passive+no_connect"))
    )
    (net (code "82") (name "unconnected-(U1005F-RESERVED-PadE3)") (class "Default")
      (node (ref "U1005") (pin "E3") (pinfunction "RESERVED_E3") (pintype "passive+no_connect"))
    )
    (net (code "83") (name "unconnected-(U1005F-RESERVED-PadE13)") (class "Default")
      (node (ref "U1005") (pin "E13") (pinfunction "RESERVED_E13") (pintype "passive+no_connect"))
    )
    (net (code "84") (name "unconnected-(U1005F-RESERVED-PadF3)") (class "Default")
      (node (ref "U1005") (pin "F3") (pinfunction "RESERVED_F3") (pintype "passive+no_connect"))
    )
    (net (code "85") (name "unconnected-(U1005F-RESERVED-PadF13)") (class "Default")
      (node (ref "U1005") (pin "F13") (pinfunction "RESERVED_F13") (pintype "passive+no_connect"))
    )
    (net (code "86") (name "unconnected-(U1005F-RESERVED-PadF14)") (class "Default")
      (node (ref "U1005") (pin "F14") (pinfunction "RESERVED_F14") (pintype "passive+no_connect"))
    )
    (net (code "87") (name "unconnected-(U1005F-RESERVED-PadF15)") (class "Default")
      (node (ref "U1005") (pin "F15") (pinfunction "RESERVED_F15") (pintype "passive+no_connect"))
    )
    (net (code "88") (name "unconnected-(U1005F-RESERVED-PadG3)") (class "Default")
      (node (ref "U1005") (pin "G3") (pinfunction "RESERVED_G3") (pintype "passive+no_connect"))
    )
    (net (code "89") (name "unconnected-(U1005F-RESERVED-PadG13)") (class "Default")
      (node (ref "U1005") (pin "G13") (pinfunction "RESERVED_G13") (pintype "passive+no_connect"))
    )
    (net (code "90") (name "unconnected-(U1005F-RESERVED-PadG14)") (class "Default")
      (node (ref "U1005") (pin "G14") (pinfunction "RESERVED_G14") (pintype "passive+no_connect"))
    )
    (net (code "91") (name "unconnected-(U1005F-RESERVED-PadH3)") (class "Default")
      (node (ref "U1005") (pin "H3") (pinfunction "RESERVED_H3") (pintype "passive+no_connect"))
    )
    (net (code "92") (name "unconnected-(U1005F-RESERVED-PadH14)") (class "Default")
      (node (ref "U1005") (pin "H14") (pinfunction "RESERVED_H14") (pintype "passive+no_connect"))
    )
    (net (code "93") (name "unconnected-(U1005F-RESERVED-PadH15)") (class "Default")
      (node (ref "U1005") (pin "H15") (pinfunction "RESERVED_H15") (pintype "passive+no_connect"))
    )
    (net (code "94") (name "unconnected-(U1005F-RESERVED-PadJ3)") (class "Default")
      (node (ref "U1005") (pin "J3") (pinfunction "RESERVED_J3") (pintype "passive+no_connect"))
    )
    (net (code "95") (name "unconnected-(U1005F-RESERVED-PadJ14)") (class "Default")
      (node (ref "U1005") (pin "J14") (pinfunction "RESERVED_J14") (pintype "passive+no_connect"))
    )
    (net (code "96") (name "unconnected-(U1005F-RESERVED-PadJ15)") (class "Default")
      (node (ref "U1005") (pin "J15") (pinfunction "RESERVED_J15") (pintype "passive+no_connect"))
    )
    (net (code "97") (name "unconnected-(U1005F-RESERVED-PadK3)") (class "Default")
      (node (ref "U1005") (pin "K3") (pinfunction "RESERVED_K3") (pintype "passive+no_connect"))
    )
    (net (code "98") (name "unconnected-(U1005F-RESERVED-PadK14)") (class "Default")
      (node (ref "U1005") (pin "K14") (pinfunction "RESERVED_K14") (pintype "passive+no_connect"))
    )
    (net (code "99") (name "unconnected-(U1005F-RESERVED-PadL3)") (class "Default")
      (node (ref "U1005") (pin "L3") (pinfunction "RESERVED_L3") (pintype "passive+no_connect"))
    )
    (net (code "100") (name "unconnected-(U1005F-RESERVED-PadN7)") (class "Default")
      (node (ref "U1005") (pin "N7") (pinfunction "RESERVED_N7") (pintype "passive+no_connect"))
    )
    (net (code "101") (name "unconnected-(U1005F-RESERVED-PadN8)") (class "Default")
      (node (ref "U1005") (pin "N8") (pinfunction "RESERVED_N8") (pintype "passive+no_connect"))
    )
    (net (code "102") (name "unconnected-(U1005F-RESERVED-PadN9)") (class "Default")
      (node (ref "U1005") (pin "N9") (pinfunction "RESERVED_N9") (pintype "passive+no_connect"))
    )
    (net (code "103") (name "unconnected-(U1005F-RESERVED-PadN10)") (class "Default")
      (node (ref "U1005") (pin "N10") (pinfunction "RESERVED_N10") (pintype "passive+no_connect"))
    )
    (net (code "104") (name "unconnected-(U1005F-RESERVED-PadN11)") (class "Default")
      (node (ref "U1005") (pin "N11") (pinfunction "RESERVED_N11") (pintype "passive+no_connect"))
    )
    (net (code "105") (name "unconnected-(U1005F-RESERVED-PadN12)") (class "Default")
      (node (ref "U1005") (pin "N12") (pinfunction "RESERVED_N12") (pintype "passive+no_connect"))
    )
    (net (code "106") (name "unconnected-(U1005F-RESERVED-PadP7)") (class "Default")
      (node (ref "U1005") (pin "P7") (pinfunction "RESERVED_P7") (pintype "passive+no_connect"))
    )
    (net (code "107") (name "unconnected-(U1005F-RESERVED-PadP11)") (class "Default")
      (node (ref "U1005") (pin "P11") (pinfunction "RESERVED_P11") (pintype "passive+no_connect"))
    )
    (net (code "108") (name "unconnected-(U1005F-RESERVED-PadP12)") (class "Default")
      (node (ref "U1005") (pin "P12") (pinfunction "RESERVED_P12") (pintype "passive+no_connect"))
    )
    (net (code "109") (name "unconnected-(U1005F-RESERVED-PadR7)") (class "Default")
      (node (ref "U1005") (pin "R7") (pinfunction "RESERVED_R7") (pintype "passive+no_connect"))
    )
    (net (code "110") (name "unconnected-(U1005G-WIFI_SD0-PadJ13)") (class "Default")
      (node (ref "U1005") (pin "J13") (pinfunction "WIFI_SD0_J13") (pintype "bidirectional+no_connect"))
    )
    (net (code "111") (name "unconnected-(U1005G-WIFI_SD1-PadM13)") (class "Default")
      (node (ref "U1005") (pin "M13") (pinfunction "WIFI_SD1_M13") (pintype "bidirectional+no_connect"))
    )
    (net (code "112") (name "unconnected-(U1005G-WIFI_SD2-PadK13)") (class "Default")
      (node (ref "U1005") (pin "K13") (pinfunction "WIFI_SD2_K13") (pintype "bidirectional+no_connect"))
    )
    (net (code "113") (name "unconnected-(U1005G-WIFI_SD3-PadH13)") (class "Default")
      (node (ref "U1005") (pin "H13") (pinfunction "WIFI_SD3_H13") (pintype "bidirectional+no_connect"))
    )
    (net (code "114") (name "unconnected-(U1005G-WIFI_SD_CLK-PadL13)") (class "Default")
      (node (ref "U1005") (pin "L13") (pinfunction "WIFI_SD_CLK_L13") (pintype "output+no_connect"))
    )
    (net (code "115") (name "unconnected-(U1005G-WIFI_SD_CMD-PadN13)") (class "Default")
      (node (ref "U1005") (pin "N13") (pinfunction "WIFI_SD_CMD_N13") (pintype "output+no_connect"))
    )
    (net (code "116") (name "unconnected-(U1005H-DVI_CLK-PadB8)") (class "Default")
      (node (ref "U1005") (pin "B8") (pinfunction "DVI_CLK_B8") (pintype "bidirectional+no_connect"))
    )
    (net (code "117") (name "unconnected-(U1005H-DVI_RX-PadB6)") (class "Default")
      (node (ref "U1005") (pin "B6") (pinfunction "DVI_RX_B6") (pintype "input+no_connect"))
    )
    (net (code "118") (name "unconnected-(U1005H-DVI_TX-PadB7)") (class "Default")
      (node (ref "U1005") (pin "B7") (pinfunction "DVI_TX_B7") (pintype "bidirectional+no_connect"))
    )
    (net (code "119") (name "unconnected-(U1005H-DVI_WA0-PadB9)") (class "Default")
      (node (ref "U1005") (pin "B9") (pinfunction "DVI_WA0_B9") (pintype "bidirectional+no_connect"))
    )
    (net (code "120") (name "unconnected-(U1006-B1-Pad12)") (class "Default")
      (node (ref "U1006") (pin "12") (pinfunction "B1_12") (pintype "bidirectional+no_connect"))
    )
    (net (code "121") (name "unconnected-(U1006-B4-Pad9)") (class "Default")
      (node (ref "U1006") (pin "9") (pinfunction "B4_9") (pintype "bidirectional+no_connect"))
    )
  )
)
